# 14-TestFixture.net
KiCad netlist of a schematic drawn in Altium Designer
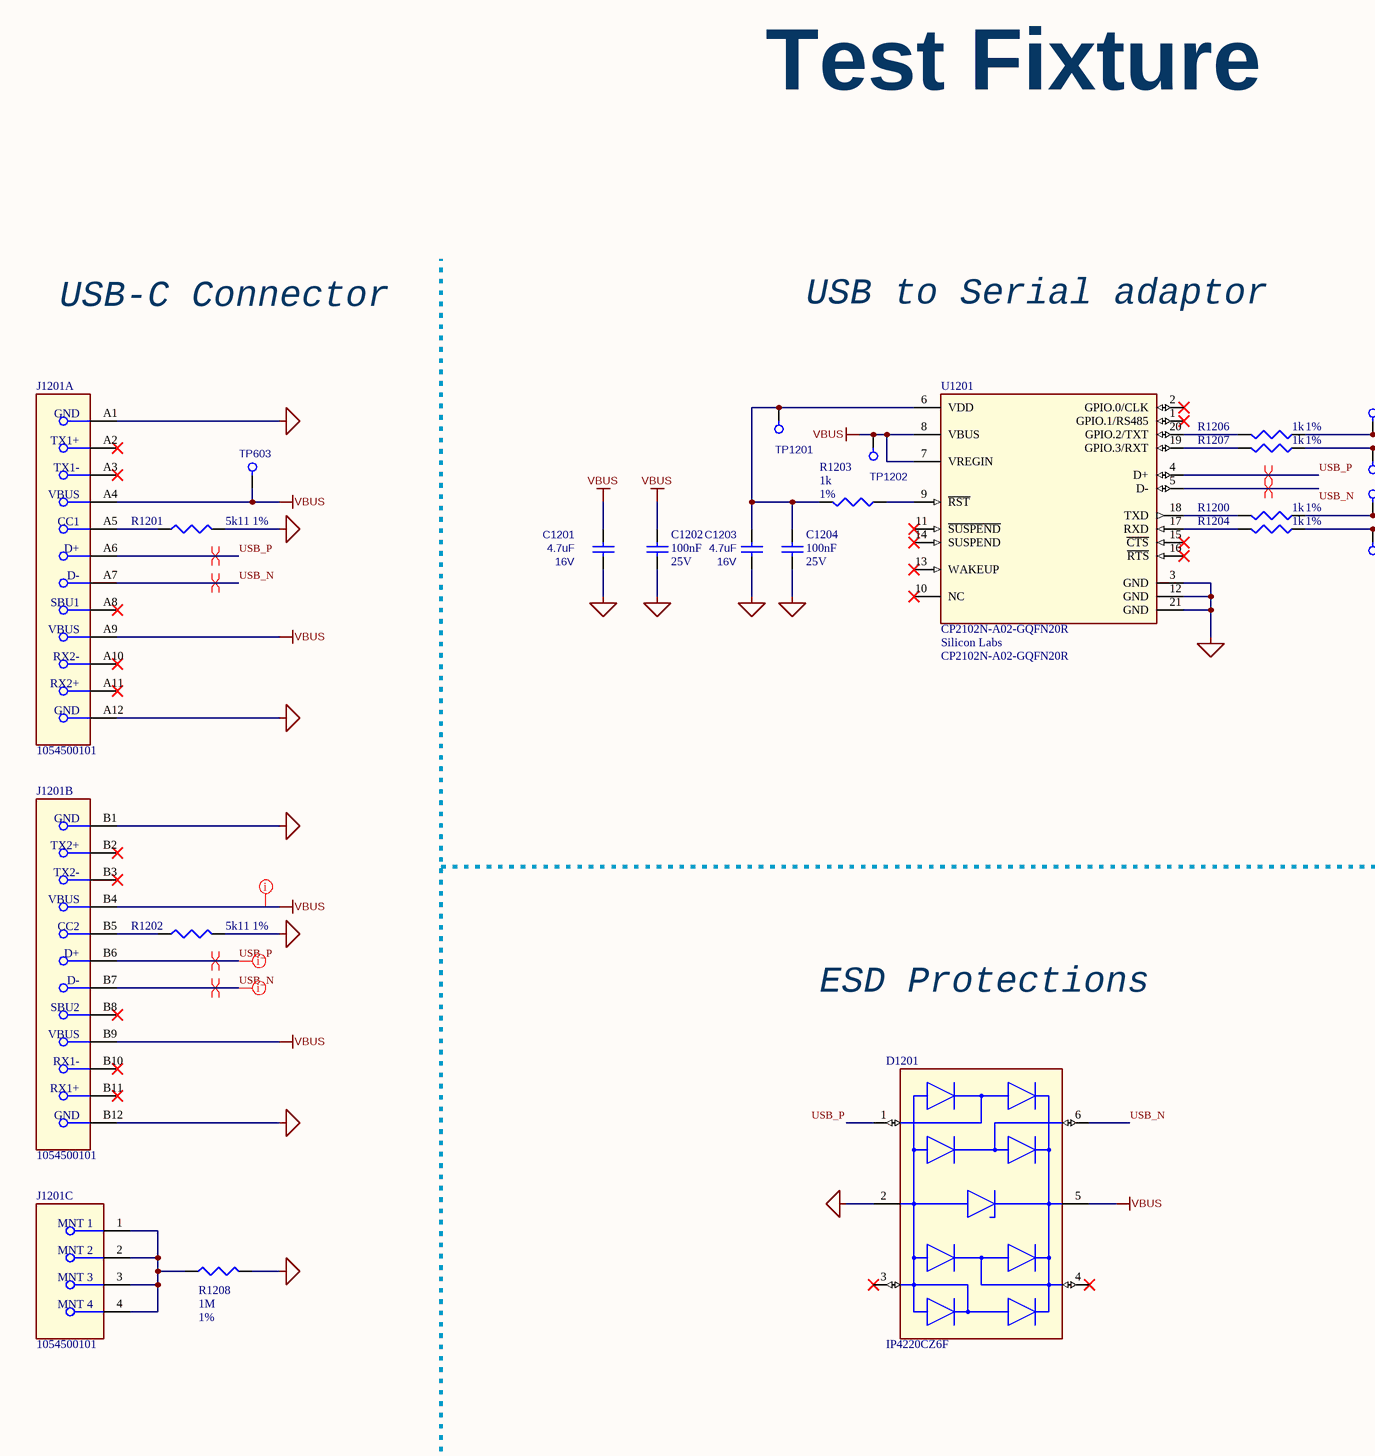
[diagram p0: 14-TestFixture.SchDoc, left]
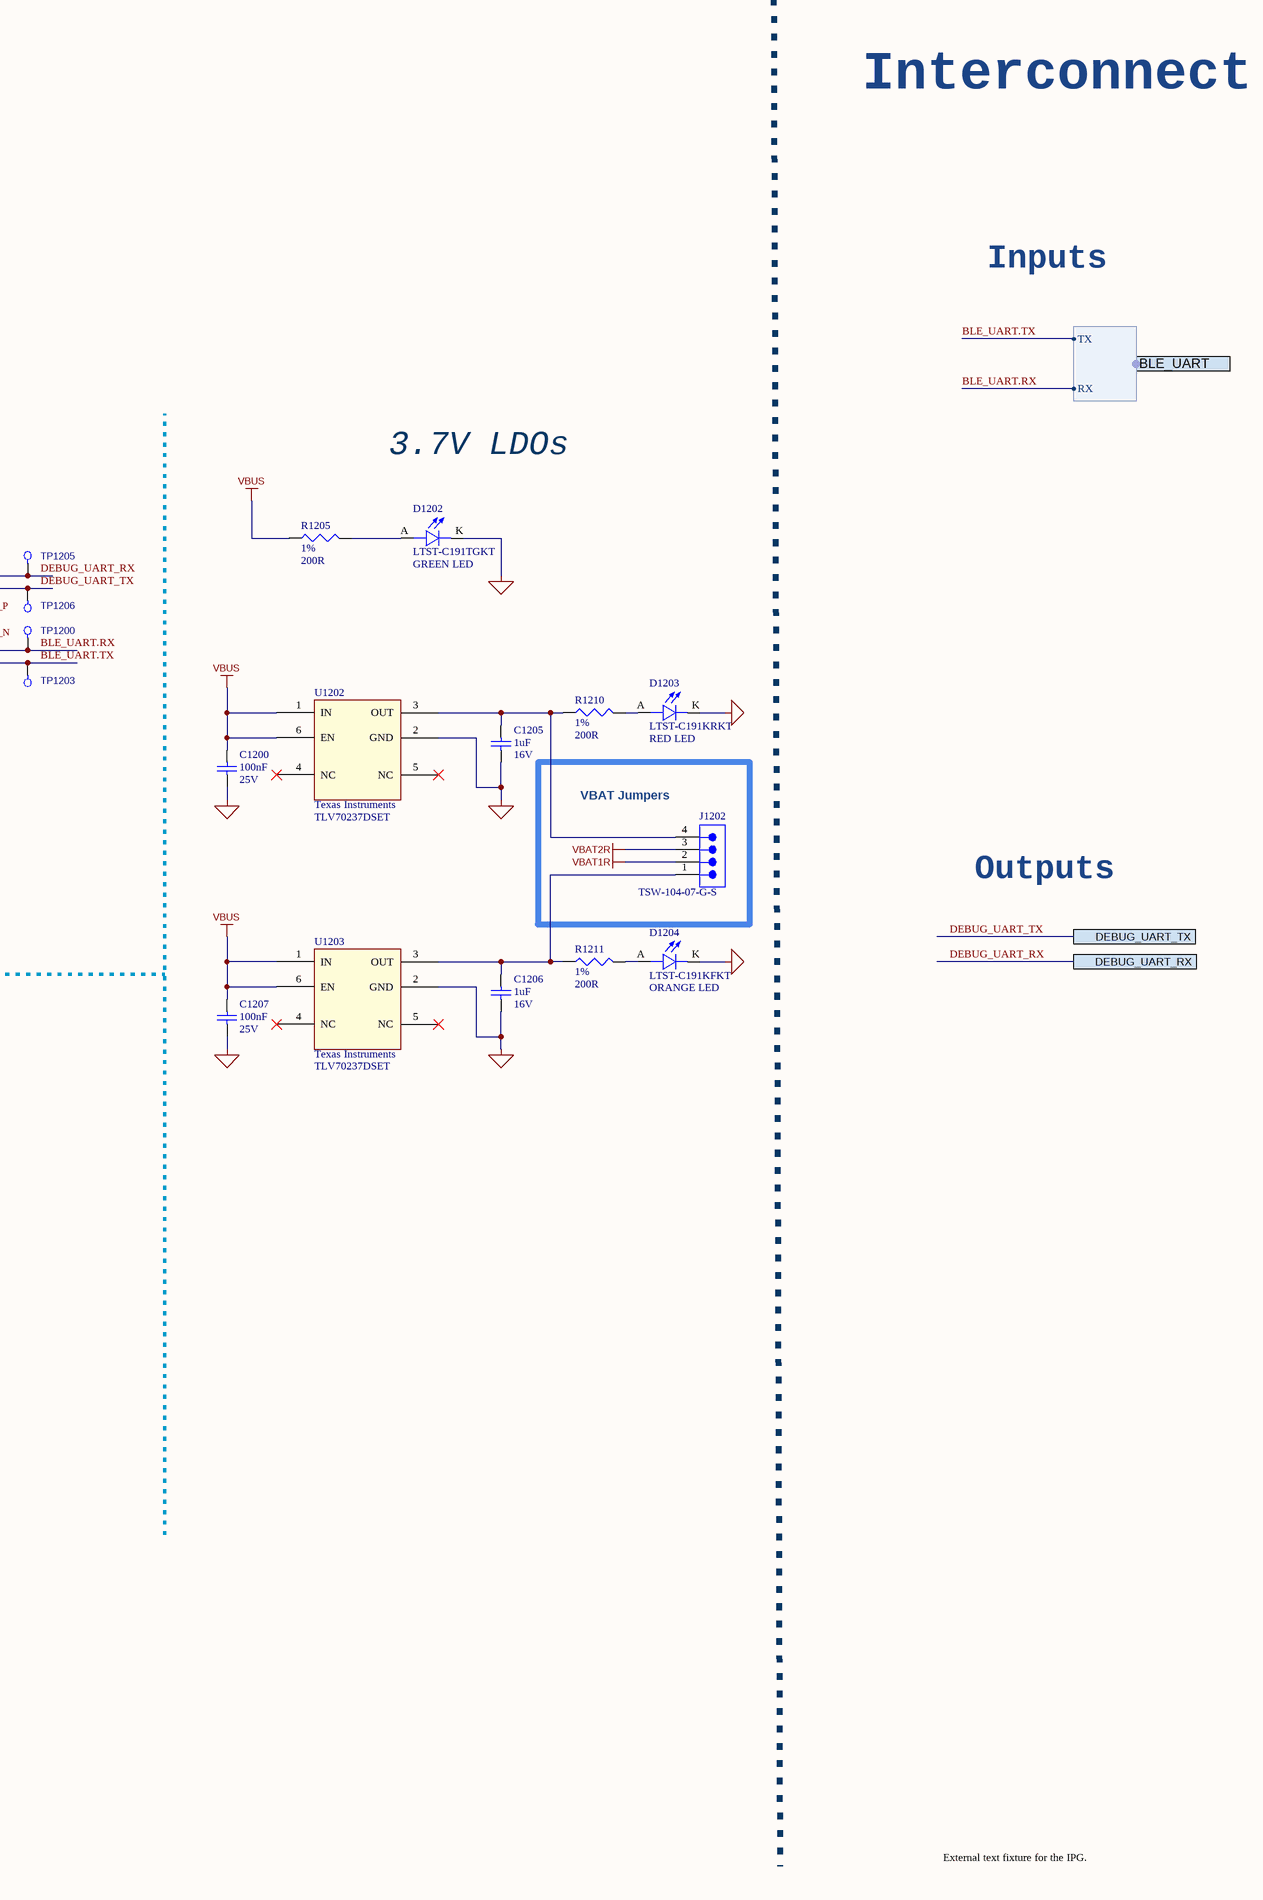
[diagram p1: 14-TestFixture.SchDoc, right]

(export (version "E")
  (design (tool "Eeschema 10.0.6"))
  (components
    (comp (ref "C1200")
      (value "100nF")
      (footprint "C0201_C")
      (fields
        (field (name "MANUFACTURER") "Murata")
        (field (name "MANUFACTURER PART NUMBER") "GRM033R61E104KE14J")
        (field (name "RATED DC VOLTAGE (URDC)") "25V")
      )
      (libsource (lib "MP-LIBRARY") (part "GRM033R61E104KE14J"))
    )
    (comp (ref "C1201")
      (value "4.7uF")
      (footprint "CAP0603_REDUCED")
      (description "Capacitor, 4.7uF, X5R, 16V, 10%, 0603, Implant-grade")
      (fields
        (field (name "MANUFACTURER") "Murata")
        (field (name "RATING") "16V")
        (field (name "MANUFACTURER PART NUMBER") "GRM188R61C475KE11")
      )
      (libsource (lib "MP-LIBRARY") (part "GRM188R61C475KE11"))
    )
    (comp (ref "C1202")
      (value "100nF")
      (footprint "C0201_C")
      (fields
        (field (name "MANUFACTURER") "Murata")
        (field (name "MANUFACTURER PART NUMBER") "GRM033R61E104KE14J")
        (field (name "RATED DC VOLTAGE (URDC)") "25V")
      )
      (libsource (lib "MP-LIBRARY") (part "GRM033R61E104KE14J"))
    )
    (comp (ref "C1203")
      (value "4.7uF")
      (footprint "CAP0603_REDUCED")
      (description "Capacitor, 4.7uF, X5R, 16V, 10%, 0603, Implant-grade")
      (fields
        (field (name "MANUFACTURER") "Murata")
        (field (name "RATING") "16V")
        (field (name "MANUFACTURER PART NUMBER") "GRM188R61C475KE11")
      )
      (libsource (lib "MP-LIBRARY") (part "GRM188R61C475KE11"))
    )
    (comp (ref "C1204")
      (value "100nF")
      (footprint "C0201_C")
      (fields
        (field (name "MANUFACTURER") "Murata")
        (field (name "MANUFACTURER PART NUMBER") "GRM033R61E104KE14J")
        (field (name "RATED DC VOLTAGE (URDC)") "25V")
      )
      (libsource (lib "MP-LIBRARY") (part "GRM033R61E104KE14J"))
    )
    (comp (ref "C1205")
      (value "1uF")
      (footprint "C0201_C")
      (fields
        (field (name "MANUFACTURER") "Murata")
        (field (name "MANUFACTURER PART NUMBER") "GRM033R61C105ME15D")
        (field (name "RATED DC VOLTAGE (URDC)") "16V")
      )
      (libsource (lib "MP-LIBRARY") (part "GRM033R61C105ME15D"))
    )
    (comp (ref "C1206")
      (value "1uF")
      (footprint "C0201_C")
      (fields
        (field (name "MANUFACTURER") "Murata")
        (field (name "MANUFACTURER PART NUMBER") "GRM033R61C105ME15D")
        (field (name "RATED DC VOLTAGE (URDC)") "16V")
      )
      (libsource (lib "MP-LIBRARY") (part "GRM033R61C105ME15D"))
    )
    (comp (ref "C1207")
      (value "100nF")
      (footprint "C0201_C")
      (fields
        (field (name "MANUFACTURER") "Murata")
        (field (name "MANUFACTURER PART NUMBER") "GRM033R61E104KE14J")
        (field (name "RATED DC VOLTAGE (URDC)") "25V")
      )
      (libsource (lib "MP-LIBRARY") (part "GRM033R61E104KE14J"))
    )
    (comp (ref "D1201")
      (value "IP4220CZ6F")
      (footprint "FP-SOT457-IPC_A")
      (description "TVS DIODE 5.5VWM 6TSOP")
      (fields (field (name "MANUFACTURER") "Nexperia"))
      (libsource (lib "MP-LIBRARY") (part "IP4220CZ6F"))
    )
    (comp (ref "D1202")
      (value "LTST-C191TGKT")
      (footprint "LEDC0603")
      (description "LED, GREEN, SMD, 0603, 3.2V, 20mA")
      (fields (field (name "MANUFACTURER") "Lite-On Inc.") (field (name "ALTIUM_VALUE") "GREEN LED"))
      (libsource (lib "MP-LIBRARY") (part "LED GREEN CLEAR SMD 0603"))
    )
    (comp (ref "D1203")
      (value "LTST-C191KRKT")
      (footprint "LEDC0603")
      (description "LED, RED, SMD, 0603, 2V, 30mA")
      (fields (field (name "MANUFACTURER") "Lite-On Inc.") (field (name "ALTIUM_VALUE") "RED LED"))
      (libsource (lib "MP-LIBRARY") (part "LED RED CLEAR SMD 0603"))
    )
    (comp (ref "D1204")
      (value "LTST-C191KFKT")
      (footprint "LEDC0603")
      (description "LED, ORANGE, SMD, 0603, 2V, 30mA")
      (fields (field (name "MANUFACTURER") "Lite-On Inc.") (field (name "ALTIUM_VALUE") "ORANGE LED"))
      (libsource (lib "MP-LIBRARY") (part "LED ORANGE CLEAR SMD 0603"))
    )
    (comp (ref "J1201")
      (value "1054500101")
      (footprint "FP-1054500101-MFG")
      (description "CONN RCP USB3.1 TYPEC 24P SMD RA")
      (fields
        (field (name "MANUFACTURER") "Molex")
        (field (name "OCTOPART") "https://octopart.com/105450-0101-molex-68082325")
      )
      (libsource (lib "MP-LIBRARY") (part "CMP-04767-000004-1"))
    )
    (comp (ref "J1202")
      (value "TSW-104-07-G-S")
      (footprint "SMTC-TSW-104-07-X-S")
      (fields (field (name "MANUFACTURER") "Samtec") (field (name "PARTNUMBER") "TSW-106-07-G-S"))
      (libsource (lib "MP-LIBRARY") (part "TSW-104-07-G-S"))
    )
    (comp (ref "R1200")
      (value "1k")
      (footprint "R0201_C")
      (fields
        (field (name "MANUFACTURER") "Vishay")
        (field (name "MANUFACTURER PART NUMBER") "CRCW02011K00FNED")
        (field (name "TOLERANCE") "1%")
        (field (name "POWER") "50mW")
      )
      (libsource (lib "MP-LIBRARY") (part "CRCW02011K00FNED"))
    )
    (comp (ref "R1201")
      (value "5k11")
      (footprint "R0201_C")
      (fields
        (field (name "TOLERANCE") "1%")
        (field (name "MANUFACTURER") "Vishay")
        (field (name "MANUFACTURER PART NUMBER") "CRCW02015K11FNED")
        (field (name "POWER") "50mW")
      )
      (libsource (lib "MP-LIBRARY") (part "CRCW02015K11FNED"))
    )
    (comp (ref "R1202")
      (value "5k11")
      (footprint "R0201_C")
      (fields
        (field (name "TOLERANCE") "1%")
        (field (name "MANUFACTURER") "Vishay")
        (field (name "MANUFACTURER PART NUMBER") "CRCW02015K11FNED")
        (field (name "POWER") "50mW")
      )
      (libsource (lib "MP-LIBRARY") (part "CRCW02015K11FNED"))
    )
    (comp (ref "R1203")
      (value "1k")
      (footprint "R0201_C")
      (fields
        (field (name "MANUFACTURER") "Vishay")
        (field (name "MANUFACTURER PART NUMBER") "CRCW02011K00FNED")
        (field (name "TOLERANCE") "1%")
        (field (name "POWER") "50mW")
      )
      (libsource (lib "MP-LIBRARY") (part "CRCW02011K00FNED"))
    )
    (comp (ref "R1204")
      (value "1k")
      (footprint "R0201_C")
      (fields
        (field (name "MANUFACTURER") "Vishay")
        (field (name "MANUFACTURER PART NUMBER") "CRCW02011K00FNED")
        (field (name "TOLERANCE") "1%")
        (field (name "POWER") "50mW")
      )
      (libsource (lib "MP-LIBRARY") (part "CRCW02011K00FNED"))
    )
    (comp (ref "R1205")
      (value "200R")
      (footprint "RES0402_REDUCED")
      (description "Resistor 200 1%, 0402, Non Implant-grade")
      (fields
        (field (name "POWER") "200 mW")
        (field (name "MANUFACTURER") "Vishay")
        (field (name "TOLERANCE") "1%")
      )
      (libsource (lib "MP-LIBRARY") (part "CRCW0402200RFKEDHP"))
    )
    (comp (ref "R1206")
      (value "1k")
      (footprint "R0201_C")
      (fields
        (field (name "MANUFACTURER") "Vishay")
        (field (name "MANUFACTURER PART NUMBER") "CRCW02011K00FNED")
        (field (name "TOLERANCE") "1%")
        (field (name "POWER") "50mW")
      )
      (libsource (lib "MP-LIBRARY") (part "CRCW02011K00FNED"))
    )
    (comp (ref "R1207")
      (value "1k")
      (footprint "R0201_C")
      (fields
        (field (name "MANUFACTURER") "Vishay")
        (field (name "MANUFACTURER PART NUMBER") "CRCW02011K00FNED")
        (field (name "TOLERANCE") "1%")
        (field (name "POWER") "50mW")
      )
      (libsource (lib "MP-LIBRARY") (part "CRCW02011K00FNED"))
    )
    (comp (ref "R1208")
      (value "1M")
      (footprint "R0201_C")
      (fields
        (field (name "MANUFACTURER") "Vishay")
        (field (name "MANUFACTURER PART NUMBER") "CRCW02011M00FNED")
        (field (name "TOLERANCE") "1%")
        (field (name "POWER") "50mW")
      )
      (libsource (lib "MP-LIBRARY") (part "CRCW02011M00FNED"))
    )
    (comp (ref "R1210")
      (value "200R")
      (footprint "RES0402_REDUCED")
      (description "Resistor 200 1%, 0402, Non Implant-grade")
      (fields
        (field (name "POWER") "200 mW")
        (field (name "MANUFACTURER") "Vishay")
        (field (name "TOLERANCE") "1%")
      )
      (libsource (lib "MP-LIBRARY") (part "CRCW0402200RFKEDHP"))
    )
    (comp (ref "R1211")
      (value "200R")
      (footprint "RES0402_REDUCED")
      (description "Resistor 200 1%, 0402, Non Implant-grade")
      (fields
        (field (name "POWER") "200 mW")
        (field (name "MANUFACTURER") "Vishay")
        (field (name "TOLERANCE") "1%")
      )
      (libsource (lib "MP-LIBRARY") (part "CRCW0402200RFKEDHP"))
    )
    (comp (ref "TP603")
      (value "Test Point")
      (footprint "testpad_0.9mm")
      (description "Test pad, 0.90mm circular pad")
      (libsource (lib "MP-LIBRARY") (part "Test Point"))
    )
    (comp (ref "TP1200")
      (value "Test Point")
      (footprint "testpad_0.9mm")
      (description "Test pad, 0.90mm circular pad")
      (libsource (lib "MP-LIBRARY") (part "Test Point"))
    )
    (comp (ref "TP1201")
      (value "Test Point")
      (footprint "testpad_0.9mm")
      (description "Test pad, 0.90mm circular pad")
      (libsource (lib "MP-LIBRARY") (part "Test Point"))
    )
    (comp (ref "TP1202")
      (value "Test Point")
      (footprint "testpad_0.9mm")
      (description "Test pad, 0.90mm circular pad")
      (libsource (lib "MP-LIBRARY") (part "Test Point"))
    )
    (comp (ref "TP1203")
      (value "Test Point")
      (footprint "testpad_0.9mm")
      (description "Test pad, 0.90mm circular pad")
      (libsource (lib "MP-LIBRARY") (part "Test Point"))
    )
    (comp (ref "TP1205")
      (value "Test Point")
      (footprint "testpad_0.9mm")
      (description "Test pad, 0.90mm circular pad")
      (libsource (lib "MP-LIBRARY") (part "Test Point"))
    )
    (comp (ref "TP1206")
      (value "Test Point")
      (footprint "testpad_0.9mm")
      (description "Test pad, 0.90mm circular pad")
      (libsource (lib "MP-LIBRARY") (part "Test Point"))
    )
    (comp (ref "U1201")
      (value "CP2102N-A02-GQFN20R")
      (footprint "FP-CP2102N-A02-GQFN20R-MFG")
      (description "IC USB TO UART BRIDGE QFN20")
      (fields
        (field (name "MANUFACTURER") "Silicon Labs")
        (field (name "ALTIUM_VALUE") "CP2102N-A02-GQFN20R")
      )
      (libsource (lib "MP-LIBRARY") (part "CP2102N-A02-GQFN20R"))
    )
    (comp (ref "U1202")
      (value "TLV70237DSET")
      (footprint "SON127P600-8N")
      (description "Fixed Positive LDO Regulator, 3.7V, 0.375V Dropout, PDSO6")
      (fields
        (field (name "MANUFACTURER") "Texas Instruments")
        (field (name "MANUFACTURER PART NUMBER") "TLV70237DSET")
      )
      (libsource (lib "MP-LIBRARY") (part "TLV70237DSET"))
    )
    (comp (ref "U1203")
      (value "TLV70237DSET")
      (footprint "SON127P600-8N")
      (description "Fixed Positive LDO Regulator, 3.7V, 0.375V Dropout, PDSO6")
      (fields
        (field (name "MANUFACTURER") "Texas Instruments")
        (field (name "MANUFACTURER PART NUMBER") "TLV70237DSET")
      )
      (libsource (lib "MP-LIBRARY") (part "TLV70237DSET"))
    )
  )
  (nets
    (net (code "2") (name "/BLE_UART.RX") (class "Default")
      (node (ref "R1200") (pin "1") (pinfunction "1_1") (pintype "passive"))
      (node (ref "TP1200") (pin "1") (pinfunction "1_1") (pintype "passive"))
    )
    (net (code "3") (name "/BLE_UART.TX") (class "Default")
      (node (ref "R1204") (pin "1") (pinfunction "1_1") (pintype "passive"))
      (node (ref "TP1203") (pin "1") (pinfunction "1_1") (pintype "passive"))
    )
    (net (code "4") (name "/DEBUG_UART_RX") (class "Default")
      (node (ref "R1206") (pin "1") (pinfunction "1_1") (pintype "passive"))
      (node (ref "TP1205") (pin "1") (pinfunction "1_1") (pintype "passive"))
    )
    (net (code "5") (name "/DEBUG_UART_TX") (class "Default")
      (node (ref "R1207") (pin "1") (pinfunction "1_1") (pintype "passive"))
      (node (ref "TP1206") (pin "1") (pinfunction "1_1") (pintype "passive"))
    )
    (net (code "6") (name "/USB_N") (class "Default")
      (node (ref "D1201") (pin "6") (pinfunction "I/O4_6") (pintype "bidirectional"))
      (node (ref "J1201") (pin "A7") (pinfunction "D-_A7") (pintype "passive"))
      (node (ref "J1201") (pin "B7") (pinfunction "D-_B7") (pintype "passive"))
      (node (ref "U1201") (pin "5") (pinfunction "D-_5") (pintype "bidirectional"))
    )
    (net (code "7") (name "/USB_P") (class "Default")
      (node (ref "D1201") (pin "1") (pinfunction "I/O1_1") (pintype "bidirectional"))
      (node (ref "J1201") (pin "A6") (pinfunction "D+_A6") (pintype "passive"))
      (node (ref "J1201") (pin "B6") (pinfunction "D+_B6") (pintype "passive"))
      (node (ref "U1201") (pin "4") (pinfunction "D+_4") (pintype "bidirectional"))
    )
    (net (code "9") (name "GND") (class "Default")
      (node (ref "C1200") (pin "1") (pinfunction "1_1") (pintype "passive"))
      (node (ref "C1201") (pin "2") (pinfunction "2_2") (pintype "passive"))
      (node (ref "C1202") (pin "1") (pinfunction "1_1") (pintype "passive"))
      (node (ref "C1203") (pin "2") (pinfunction "2_2") (pintype "passive"))
      (node (ref "C1204") (pin "1") (pinfunction "1_1") (pintype "passive"))
      (node (ref "C1205") (pin "2") (pinfunction "2_2") (pintype "passive"))
      (node (ref "C1206") (pin "1") (pinfunction "1_1") (pintype "passive"))
      (node (ref "C1207") (pin "1") (pinfunction "1_1") (pintype "passive"))
      (node (ref "D1201") (pin "2") (pinfunction "GND_2") (pintype "power_in"))
      (node (ref "D1202") (pin "K") (pinfunction "K_K") (pintype "passive"))
      (node (ref "D1203") (pin "K") (pinfunction "K_K") (pintype "passive"))
      (node (ref "D1204") (pin "K") (pinfunction "K_K") (pintype "passive"))
      (node (ref "J1201") (pin "A1") (pinfunction "GND_A1") (pintype "passive"))
      (node (ref "J1201") (pin "A12") (pinfunction "GND_A12") (pintype "passive"))
      (node (ref "J1201") (pin "B1") (pinfunction "GND_B1") (pintype "passive"))
      (node (ref "J1201") (pin "B12") (pinfunction "GND_B12") (pintype "passive"))
      (node (ref "R1201") (pin "2") (pinfunction "2_2") (pintype "passive"))
      (node (ref "R1202") (pin "2") (pinfunction "2_2") (pintype "passive"))
      (node (ref "R1208") (pin "2") (pinfunction "2_2") (pintype "passive"))
      (node (ref "U1201") (pin "12") (pinfunction "GND_12") (pintype "power_in"))
      (node (ref "U1201") (pin "21") (pinfunction "GND_21") (pintype "power_in"))
      (node (ref "U1201") (pin "3") (pinfunction "GND_3") (pintype "power_in"))
      (node (ref "U1202") (pin "2") (pinfunction "GND_2") (pintype "passive"))
      (node (ref "U1203") (pin "2") (pinfunction "GND_2") (pintype "passive"))
    )
    (net (code "10") (name "Net-(D1202-PadA)") (class "Default")
      (node (ref "D1202") (pin "A") (pinfunction "A_A") (pintype "passive"))
      (node (ref "R1205") (pin "2") (pinfunction "2_2") (pintype "passive"))
    )
    (net (code "11") (name "Net-(D1203-PadA)") (class "Default")
      (node (ref "D1203") (pin "A") (pinfunction "A_A") (pintype "passive"))
      (node (ref "R1210") (pin "2") (pinfunction "2_2") (pintype "passive"))
    )
    (net (code "12") (name "Net-(D1204-PadA)") (class "Default")
      (node (ref "D1204") (pin "A") (pinfunction "A_A") (pintype "passive"))
      (node (ref "R1211") (pin "2") (pinfunction "2_2") (pintype "passive"))
    )
    (net (code "13") (name "Net-(J1201A-CC1)") (class "Default")
      (node (ref "J1201") (pin "A5") (pinfunction "CC1_A5") (pintype "passive"))
      (node (ref "R1201") (pin "1") (pinfunction "1_1") (pintype "passive"))
    )
    (net (code "14") (name "Net-(J1201B-CC2)") (class "Default")
      (node (ref "J1201") (pin "B5") (pinfunction "CC2_B5") (pintype "passive"))
      (node (ref "R1202") (pin "1") (pinfunction "1_1") (pintype "passive"))
    )
    (net (code "15") (name "Net-(J1201C-MNT_1)") (class "Default")
      (node (ref "J1201") (pin "1") (pinfunction "MNT_1_1") (pintype "passive"))
      (node (ref "J1201") (pin "2") (pinfunction "MNT_2_2") (pintype "passive"))
      (node (ref "J1201") (pin "3") (pinfunction "MNT_3_3") (pintype "passive"))
      (node (ref "J1201") (pin "4") (pinfunction "MNT_4_4") (pintype "passive"))
      (node (ref "R1208") (pin "1") (pinfunction "1_1") (pintype "passive"))
    )
    (net (code "16") (name "Net-(U1201-GPIO.2{slash}TXT)") (class "Default")
      (node (ref "R1206") (pin "2") (pinfunction "2_2") (pintype "passive"))
      (node (ref "U1201") (pin "20") (pinfunction "GPIO.2/TXT_20") (pintype "bidirectional"))
    )
    (net (code "17") (name "Net-(U1201-GPIO.3{slash}RXT)") (class "Default")
      (node (ref "R1207") (pin "2") (pinfunction "2_2") (pintype "passive"))
      (node (ref "U1201") (pin "19") (pinfunction "GPIO.3/RXT_19") (pintype "bidirectional"))
    )
    (net (code "18") (name "Net-(U1201-RXD)") (class "Default")
      (node (ref "R1204") (pin "2") (pinfunction "2_2") (pintype "passive"))
      (node (ref "U1201") (pin "17") (pinfunction "RXD_17") (pintype "input"))
    )
    (net (code "19") (name "Net-(U1201-TXD)") (class "Default")
      (node (ref "R1200") (pin "2") (pinfunction "2_2") (pintype "passive"))
      (node (ref "U1201") (pin "18") (pinfunction "TXD_18") (pintype "output"))
    )
    (net (code "20") (name "Net-(U1201-VDD)") (class "Default")
      (node (ref "C1203") (pin "1") (pinfunction "1_1") (pintype "passive"))
      (node (ref "C1204") (pin "2") (pinfunction "2_2") (pintype "passive"))
      (node (ref "R1203") (pin "2") (pinfunction "2_2") (pintype "passive"))
      (node (ref "TP1201") (pin "1") (pinfunction "1_1") (pintype "passive"))
      (node (ref "U1201") (pin "6") (pinfunction "VDD_6") (pintype "power_in"))
    )
    (net (code "21") (name "Net-(U1201-~{RST})") (class "Default")
      (node (ref "R1203") (pin "1") (pinfunction "1_1") (pintype "passive"))
      (node (ref "U1201") (pin "9") (pinfunction "~{RST}_9") (pintype "input"))
    )
    (net (code "22") (name "Net-(U1202-OUT)") (class "Default")
      (node (ref "C1205") (pin "1") (pinfunction "1_1") (pintype "passive"))
      (node (ref "J1202") (pin "4") (pinfunction "4_4") (pintype "passive"))
      (node (ref "R1210") (pin "1") (pinfunction "1_1") (pintype "passive"))
      (node (ref "U1202") (pin "3") (pinfunction "OUT_3") (pintype "passive"))
    )
    (net (code "23") (name "Net-(U1203-OUT)") (class "Default")
      (node (ref "C1206") (pin "2") (pinfunction "2_2") (pintype "passive"))
      (node (ref "J1202") (pin "1") (pinfunction "1_1") (pintype "passive"))
      (node (ref "R1211") (pin "1") (pinfunction "1_1") (pintype "passive"))
      (node (ref "U1203") (pin "3") (pinfunction "OUT_3") (pintype "passive"))
    )
    (net (code "24") (name "VBAT1R") (class "Default")
      (node (ref "J1202") (pin "2") (pinfunction "2_2") (pintype "passive"))
    )
    (net (code "25") (name "VBAT2R") (class "Default")
      (node (ref "J1202") (pin "3") (pinfunction "3_3") (pintype "passive"))
    )
    (net (code "26") (name "VBUS") (class "Default")
      (node (ref "C1200") (pin "2") (pinfunction "2_2") (pintype "passive"))
      (node (ref "C1201") (pin "1") (pinfunction "1_1") (pintype "passive"))
      (node (ref "C1202") (pin "2") (pinfunction "2_2") (pintype "passive"))
      (node (ref "C1207") (pin "2") (pinfunction "2_2") (pintype "passive"))
      (node (ref "D1201") (pin "5") (pinfunction "VP_5") (pintype "power_in"))
      (node (ref "J1201") (pin "A4") (pinfunction "VBUS_A4") (pintype "passive"))
      (node (ref "J1201") (pin "A9") (pinfunction "VBUS_A9") (pintype "passive"))
      (node (ref "J1201") (pin "B4") (pinfunction "VBUS_B4") (pintype "passive"))
      (node (ref "J1201") (pin "B9") (pinfunction "VBUS_B9") (pintype "passive"))
      (node (ref "R1205") (pin "1") (pinfunction "1_1") (pintype "passive"))
      (node (ref "TP1202") (pin "1") (pinfunction "1_1") (pintype "passive"))
      (node (ref "TP603") (pin "1") (pinfunction "1_1") (pintype "passive"))
      (node (ref "U1201") (pin "7") (pinfunction "VREGIN_7") (pintype "passive"))
      (node (ref "U1201") (pin "8") (pinfunction "VBUS_8") (pintype "power_in"))
      (node (ref "U1202") (pin "1") (pinfunction "IN_1") (pintype "passive"))
      (node (ref "U1202") (pin "6") (pinfunction "EN_6") (pintype "passive"))
      (node (ref "U1203") (pin "1") (pinfunction "IN_1") (pintype "passive"))
      (node (ref "U1203") (pin "6") (pinfunction "EN_6") (pintype "passive"))
    )
    (net (code "27") (name "unconnected-(D1201-I{slash}O2-Pad3)") (class "Default")
      (node (ref "D1201") (pin "3") (pinfunction "I/O2_3") (pintype "bidirectional+no_connect"))
    )
    (net (code "28") (name "unconnected-(D1201-I{slash}O3-Pad4)") (class "Default")
      (node (ref "D1201") (pin "4") (pinfunction "I/O3_4") (pintype "bidirectional+no_connect"))
    )
    (net (code "29") (name "unconnected-(J1201A-RX2+-PadA11)") (class "Default")
      (node (ref "J1201") (pin "A11") (pinfunction "RX2+_A11") (pintype "passive+no_connect"))
    )
    (net (code "30") (name "unconnected-(J1201A-RX2--PadA10)") (class "Default")
      (node (ref "J1201") (pin "A10") (pinfunction "RX2-_A10") (pintype "passive+no_connect"))
    )
    (net (code "31") (name "unconnected-(J1201A-SBU1-PadA8)") (class "Default")
      (node (ref "J1201") (pin "A8") (pinfunction "SBU1_A8") (pintype "passive+no_connect"))
    )
    (net (code "32") (name "unconnected-(J1201A-TX1+-PadA2)") (class "Default")
      (node (ref "J1201") (pin "A2") (pinfunction "TX1+_A2") (pintype "passive+no_connect"))
    )
    (net (code "33") (name "unconnected-(J1201A-TX1--PadA3)") (class "Default")
      (node (ref "J1201") (pin "A3") (pinfunction "TX1-_A3") (pintype "passive+no_connect"))
    )
    (net (code "34") (name "unconnected-(J1201B-RX1+-PadB11)") (class "Default")
      (node (ref "J1201") (pin "B11") (pinfunction "RX1+_B11") (pintype "passive+no_connect"))
    )
    (net (code "35") (name "unconnected-(J1201B-RX1--PadB10)") (class "Default")
      (node (ref "J1201") (pin "B10") (pinfunction "RX1-_B10") (pintype "passive+no_connect"))
    )
    (net (code "36") (name "unconnected-(J1201B-SBU2-PadB8)") (class "Default")
      (node (ref "J1201") (pin "B8") (pinfunction "SBU2_B8") (pintype "passive+no_connect"))
    )
    (net (code "37") (name "unconnected-(J1201B-TX2+-PadB2)") (class "Default")
      (node (ref "J1201") (pin "B2") (pinfunction "TX2+_B2") (pintype "passive+no_connect"))
    )
    (net (code "38") (name "unconnected-(J1201B-TX2--PadB3)") (class "Default")
      (node (ref "J1201") (pin "B3") (pinfunction "TX2-_B3") (pintype "passive+no_connect"))
    )
    (net (code "39") (name "unconnected-(U1201-GPIO.0{slash}CLK-Pad2)") (class "Default")
      (node (ref "U1201") (pin "2") (pinfunction "GPIO.0/CLK_2") (pintype "bidirectional+no_connect"))
    )
    (net (code "40") (name "unconnected-(U1201-GPIO.1{slash}RS485-Pad1)") (class "Default")
      (node (ref "U1201") (pin "1") (pinfunction "GPIO.1/RS485_1") (pintype "bidirectional+no_connect"))
    )
    (net (code "41") (name "unconnected-(U1201-NC-Pad10)") (class "Default")
      (node (ref "U1201") (pin "10") (pinfunction "NC_10") (pintype "passive+no_connect"))
    )
    (net (code "42") (name "unconnected-(U1201-SUSPEND-Pad14)") (class "Default")
      (node (ref "U1201") (pin "14") (pinfunction "SUSPEND_14") (pintype "input+no_connect"))
    )
    (net (code "43") (name "unconnected-(U1201-WAKEUP-Pad13)") (class "Default")
      (node (ref "U1201") (pin "13") (pinfunction "WAKEUP_13") (pintype "input+no_connect"))
    )
    (net (code "44") (name "unconnected-(U1201-~{CTS}-Pad15)") (class "Default")
      (node (ref "U1201") (pin "15") (pinfunction "~{CTS}_15") (pintype "input+no_connect"))
    )
    (net (code "45") (name "unconnected-(U1201-~{RTS}-Pad16)") (class "Default")
      (node (ref "U1201") (pin "16") (pinfunction "~{RTS}_16") (pintype "input+no_connect"))
    )
    (net (code "46") (name "unconnected-(U1201-~{SUSPEND}-Pad11)") (class "Default")
      (node (ref "U1201") (pin "11") (pinfunction "~{SUSPEND}_11") (pintype "input+no_connect"))
    )
    (net (code "47") (name "unconnected-(U1202-NC-Pad4)") (class "Default")
      (node (ref "U1202") (pin "4") (pinfunction "NC_4") (pintype "passive+no_connect"))
    )
    (net (code "48") (name "unconnected-(U1202-NC-Pad5)") (class "Default")
      (node (ref "U1202") (pin "5") (pinfunction "NC_5") (pintype "passive+no_connect"))
    )
    (net (code "49") (name "unconnected-(U1203-NC-Pad4)") (class "Default")
      (node (ref "U1203") (pin "4") (pinfunction "NC_4") (pintype "passive+no_connect"))
    )
    (net (code "50") (name "unconnected-(U1203-NC-Pad5)") (class "Default")
      (node (ref "U1203") (pin "5") (pinfunction "NC_5") (pintype "passive+no_connect"))
    )
  )
)
